# ET2.net
KiCad netlist of a schematic drawn in EAGLE
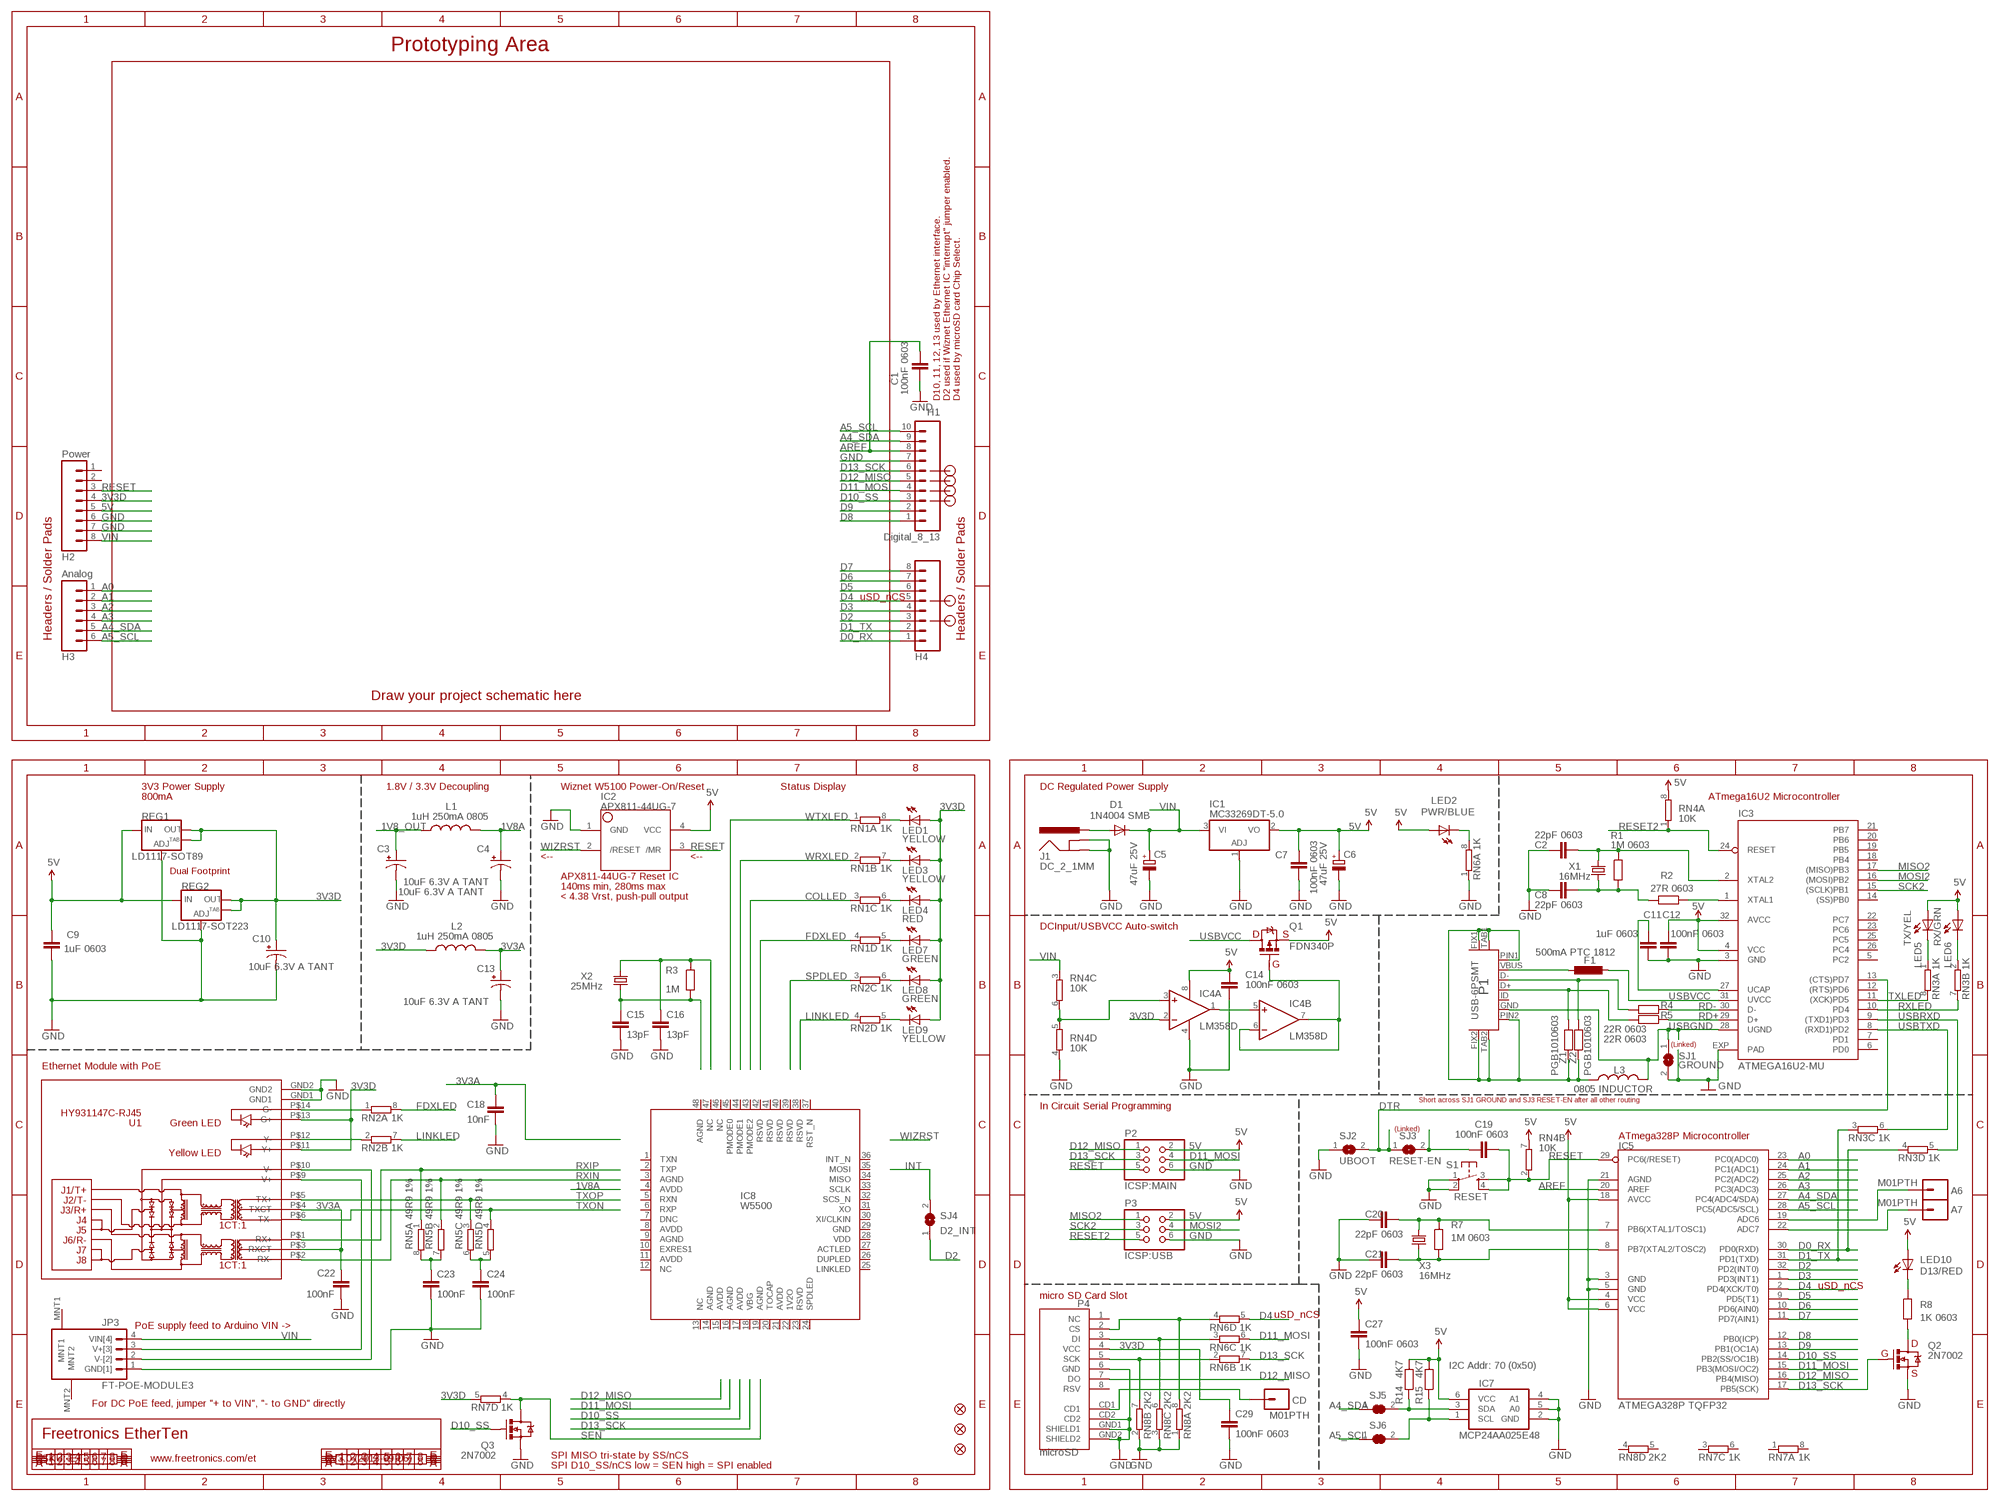
[diagram p0: schematic, sheet 1]

(export (version "E")
  (design (tool "Eeschema 10.0.6"))
  (components
    (comp (ref "A6")
      (value "M01PTH")
      (footprint "eagle-import:1X01")
      (libsource (lib "eagle-import") (part "M01PTH"))
    )
    (comp (ref "A7")
      (value "M01PTH")
      (footprint "eagle-import:1X01")
      (libsource (lib "eagle-import") (part "M01PTH"))
    )
    (comp (ref "C1")
      (value "100nF 0603")
      (footprint "eagle-import:0603")
      (libsource (lib "eagle-import") (part "CAP0603"))
    )
    (comp (ref "C2")
      (value "22pF 0603")
      (footprint "eagle-import:0603")
      (libsource (lib "eagle-import") (part "CAP0603"))
    )
    (comp (ref "C3")
      (value "10uF 6.3V A TANT")
      (footprint "eagle-import:EIA3216")
      (libsource (lib "eagle-import") (part "CAP_POL1206"))
    )
    (comp (ref "C4")
      (value "10uF 6.3V A TANT")
      (footprint "eagle-import:EIA3216")
      (libsource (lib "eagle-import") (part "CAP_POL1206"))
    )
    (comp (ref "C5")
      (value "47uF 25V")
      (footprint "eagle-import:PANASONIC_D")
      (libsource (lib "eagle-import") (part "CPOL-EUD"))
    )
    (comp (ref "C6")
      (value "47uF 25V")
      (footprint "eagle-import:PANASONIC_D")
      (libsource (lib "eagle-import") (part "CPOL-EUD"))
    )
    (comp (ref "C7")
      (value "100nF 0603")
      (footprint "eagle-import:0603")
      (libsource (lib "eagle-import") (part "CAP0603"))
    )
    (comp (ref "C8")
      (value "22pF 0603")
      (footprint "eagle-import:0603")
      (libsource (lib "eagle-import") (part "CAP0603"))
    )
    (comp (ref "C9")
      (value "1uF 0603")
      (footprint "eagle-import:0603")
      (libsource (lib "eagle-import") (part "CAP0603"))
    )
    (comp (ref "C10")
      (value "10uF 6.3V A TANT")
      (footprint "eagle-import:EIA3216")
      (libsource (lib "eagle-import") (part "CAP_POL1206"))
    )
    (comp (ref "C11")
      (value "1uF 0603")
      (footprint "eagle-import:0603")
      (libsource (lib "eagle-import") (part "CAP0603"))
    )
    (comp (ref "C12")
      (value "100nF 0603")
      (footprint "eagle-import:0603")
      (libsource (lib "eagle-import") (part "CAP0603"))
    )
    (comp (ref "C13")
      (value "10uF 6.3V A TANT")
      (footprint "eagle-import:EIA3216")
      (libsource (lib "eagle-import") (part "CAP_POL1206"))
    )
    (comp (ref "C14")
      (value "100nF 0603")
      (footprint "eagle-import:0603")
      (libsource (lib "eagle-import") (part "CAP0603"))
    )
    (comp (ref "C15")
      (value "13pF")
      (footprint "eagle-import:0603")
      (libsource (lib "eagle-import") (part "CAP0603"))
    )
    (comp (ref "C16")
      (value "13pF")
      (footprint "eagle-import:0603")
      (libsource (lib "eagle-import") (part "CAP0603"))
    )
    (comp (ref "C18")
      (value "10nF")
      (footprint "eagle-import:0603")
      (libsource (lib "eagle-import") (part "CAP0603"))
    )
    (comp (ref "C19")
      (value "100nF 0603")
      (footprint "eagle-import:0603")
      (libsource (lib "eagle-import") (part "CAP0603"))
    )
    (comp (ref "C20")
      (value "22pF 0603")
      (footprint "eagle-import:0603")
      (libsource (lib "eagle-import") (part "CAP0603"))
    )
    (comp (ref "C21")
      (value "22pF 0603")
      (footprint "eagle-import:0603")
      (libsource (lib "eagle-import") (part "CAP0603"))
    )
    (comp (ref "C22")
      (value "100nF")
      (footprint "eagle-import:0603")
      (libsource (lib "eagle-import") (part "CAP0603"))
    )
    (comp (ref "C23")
      (value "100nF")
      (footprint "eagle-import:0603")
      (libsource (lib "eagle-import") (part "CAP0603"))
    )
    (comp (ref "C24")
      (value "100nF")
      (footprint "eagle-import:0603")
      (libsource (lib "eagle-import") (part "CAP0603"))
    )
    (comp (ref "C27")
      (value "100nF 0603")
      (footprint "eagle-import:0603")
      (libsource (lib "eagle-import") (part "CAP0603"))
    )
    (comp (ref "C29")
      (value "100nF 0603")
      (footprint "eagle-import:0603")
      (libsource (lib "eagle-import") (part "CAP0603"))
    )
    (comp (ref "CD")
      (value "M01PTH")
      (footprint "eagle-import:1X01")
      (libsource (lib "eagle-import") (part "M01PTH"))
    )
    (comp (ref "D1")
      (value "1N4004 SMB")
      (footprint "eagle-import:SMB-DIODE")
      (libsource (lib "eagle-import") (part "DIODESMB"))
    )
    (comp (ref "F1")
      (value "500mA PTC 1812")
      (footprint "eagle-import:L1812")
      (libsource (lib "eagle-import") (part "L-EUL1812"))
    )
    (comp (ref "FID1")
      (value "FIDUCIAL1X2.5")
      (footprint "eagle-import:FIDUCIAL-1X2.5")
      (libsource (lib "eagle-import") (part "FIDUCIAL1X2.5"))
    )
    (comp (ref "FID2")
      (value "FIDUCIAL1X2.5")
      (footprint "eagle-import:FIDUCIAL-1X2.5")
      (libsource (lib "eagle-import") (part "FIDUCIAL1X2.5"))
    )
    (comp (ref "FID3")
      (value "FIDUCIAL1X2.5")
      (footprint "eagle-import:FIDUCIAL-1X2.5")
      (libsource (lib "eagle-import") (part "FIDUCIAL1X2.5"))
    )
    (comp (ref "H1")
      (value "Digital_8_13")
      (footprint "eagle-import:1X10")
      (libsource (lib "eagle-import") (part "M100.1"))
    )
    (comp (ref "H2")
      (value "Power")
      (footprint "eagle-import:1X08")
      (libsource (lib "eagle-import") (part "freetronics-master-v1_M08"))
    )
    (comp (ref "H3")
      (value "Analog")
      (footprint "eagle-import:1X06")
      (libsource (lib "eagle-import") (part "M06SIP"))
    )
    (comp (ref "H4")
      (value "Digital_0_7")
      (footprint "eagle-import:1X08")
      (libsource (lib "eagle-import") (part "M08"))
    )
    (comp (ref "IC1")
      (value "MC33269DT-5.0")
      (footprint "eagle-import:DPACK")
      (libsource (lib "eagle-import") (part "MC33269?D-5.0"))
    )
    (comp (ref "IC2")
      (value "APX811-44UG-7")
      (footprint "eagle-import:SOT143-R")
      (libsource (lib "eagle-import") (part "APX81X-RESET-IC"))
    )
    (comp (ref "IC3")
      (value "ATMEGA16U2-MU")
      (footprint "eagle-import:ATMEL_QFN32")
      (libsource (lib "eagle-import") (part "ATMEL_ATMEGA8U2-MUQFN"))
    )
    (comp (ref "IC4")
      (value "LM358D")
      (footprint "eagle-import:SO08")
      (libsource (lib "eagle-import") (part "LM358D"))
    )
    (comp (ref "IC5")
      (value "ATMEGA328P TQFP32")
      (footprint "eagle-import:TQFP32-08")
      (libsource (lib "eagle-import") (part "AVR-MEGA8-AI"))
    )
    (comp (ref "IC7")
      (value "MCP24AA025E48")
      (footprint "eagle-import:SOT23-6")
      (libsource (lib "eagle-import") (part "MCP24AA025E48"))
    )
    (comp (ref "IC8")
      (value "W5500")
      (footprint "eagle-import:W5500")
      (libsource (lib "eagle-import") (part "W5500"))
    )
    (comp (ref "J1")
      (value "DC_2_1MM")
      (footprint "eagle-import:POWER_JACK_PTH")
      (libsource (lib "eagle-import") (part "POWER_JACKPTH"))
    )
    (comp (ref "JP3")
      (value "FT-POE-MODULE3")
      (footprint "eagle-import:FT-POE-MODULE-NOLABEL")
      (libsource (lib "eagle-import") (part "FT-POE-MODULE3"))
    )
    (comp (ref "L1")
      (value "1uH 250mA 0805")
      (footprint "eagle-import:L2012C")
      (libsource (lib "eagle-import") (part "L-USL2012C"))
    )
    (comp (ref "L2")
      (value "1uH 250mA 0805")
      (footprint "eagle-import:L2012C")
      (libsource (lib "eagle-import") (part "L-USL2012C"))
    )
    (comp (ref "L3")
      (value "0805 INDUCTOR")
      (footprint "eagle-import:0805-LARGE")
      (libsource (lib "eagle-import") (part "INDUCTOR0805-LARGE"))
    )
    (comp (ref "LED1")
      (value "YELLOW")
      (footprint "eagle-import:LED-0603")
      (libsource (lib "eagle-import") (part "LED0603"))
    )
    (comp (ref "LED2")
      (value "PWR/BLUE")
      (footprint "eagle-import:LED-0603")
      (libsource (lib "eagle-import") (part "LED0603"))
    )
    (comp (ref "LED3")
      (value "YELLOW")
      (footprint "eagle-import:LED-0603")
      (libsource (lib "eagle-import") (part "LED0603"))
    )
    (comp (ref "LED4")
      (value "RED")
      (footprint "eagle-import:LED-0603")
      (libsource (lib "eagle-import") (part "LED0603"))
    )
    (comp (ref "LED5")
      (value "TX/YEL")
      (footprint "eagle-import:LED-0603")
      (libsource (lib "eagle-import") (part "LED0603"))
    )
    (comp (ref "LED6")
      (value "RX/GRN")
      (footprint "eagle-import:LED-0603")
      (libsource (lib "eagle-import") (part "LED0603"))
    )
    (comp (ref "LED7")
      (value "GREEN")
      (footprint "eagle-import:LED-0603")
      (libsource (lib "eagle-import") (part "LED0603"))
    )
    (comp (ref "LED8")
      (value "GREEN")
      (footprint "eagle-import:LED-0603")
      (libsource (lib "eagle-import") (part "LED0603"))
    )
    (comp (ref "LED9")
      (value "YELLOW")
      (footprint "eagle-import:LED-0603")
      (libsource (lib "eagle-import") (part "LED0603"))
    )
    (comp (ref "LED10")
      (value "D13/RED")
      (footprint "eagle-import:LED-0603")
      (libsource (lib "eagle-import") (part "LED0603"))
    )
    (comp (ref "P1")
      (value "USB-6PSMT")
      (footprint "eagle-import:USB-MICROB-MB05PMXX")
      (libsource (lib "eagle-import") (part "USB-6PSMT"))
    )
    (comp (ref "P2")
      (value "ICSP:MAIN")
      (footprint "eagle-import:2X03")
      (libsource (lib "eagle-import") (part "PINHD-2X3"))
    )
    (comp (ref "P3")
      (value "ICSP:USB")
      (footprint "eagle-import:2X03")
      (libsource (lib "eagle-import") (part "PINHD-2X3"))
    )
    (comp (ref "P4")
      (value "microSD")
      (footprint "eagle-import:MICRO-SD-SOCKET-PP")
      (libsource (lib "eagle-import") (part "USD-SOCKETNEW"))
    )
    (comp (ref "Q1")
      (value "FDN340P")
      (footprint "eagle-import:SOT23")
      (libsource (lib "eagle-import") (part "MOSFET-PCHANNEL"))
    )
    (comp (ref "Q2")
      (value "2N7002")
      (footprint "eagle-import:SOT23-3")
      (libsource (lib "eagle-import") (part "MOSFET-NCHANNELSMD"))
    )
    (comp (ref "Q3")
      (value "2N7002")
      (footprint "eagle-import:SOT23-3")
      (libsource (lib "eagle-import") (part "MOSFET-NCHANNELSMD"))
    )
    (comp (ref "R1")
      (value "1M 0603")
      (footprint "eagle-import:0603")
      (libsource (lib "eagle-import") (part "RESISTOR0603"))
    )
    (comp (ref "R2")
      (value "27R 0603")
      (footprint "eagle-import:0603")
      (libsource (lib "eagle-import") (part "RESISTOR0603"))
    )
    (comp (ref "R3")
      (value "1M")
      (footprint "eagle-import:0603")
      (libsource (lib "eagle-import") (part "RESISTOR0603"))
    )
    (comp (ref "R4")
      (value "22R 0603")
      (footprint "eagle-import:0603")
      (libsource (lib "eagle-import") (part "RESISTOR0603"))
    )
    (comp (ref "R5")
      (value "22R 0603")
      (footprint "eagle-import:0603")
      (libsource (lib "eagle-import") (part "RESISTOR0603"))
    )
    (comp (ref "R7")
      (value "1M 0603")
      (footprint "eagle-import:0603")
      (libsource (lib "eagle-import") (part "RESISTOR0603"))
    )
    (comp (ref "R8")
      (value "1K 0603")
      (footprint "eagle-import:0603")
      (libsource (lib "eagle-import") (part "RESISTOR0603"))
    )
    (comp (ref "R14")
      (value "4K7")
      (footprint "eagle-import:0603")
      (libsource (lib "eagle-import") (part "freetronics-master-v1.1_RESISTOR0603"))
    )
    (comp (ref "R15")
      (value "4K7")
      (footprint "eagle-import:0603")
      (libsource (lib "eagle-import") (part "freetronics-master-v1.1_RESISTOR0603"))
    )
    (comp (ref "REG1")
      (value "LD1117-SOT89")
      (footprint "eagle-import:SOT89")
      (libsource (lib "eagle-import") (part "V_REG_LM1117SOT89"))
    )
    (comp (ref "REG2")
      (value "LD1117-SOT223")
      (footprint "eagle-import:SOT223")
      (libsource (lib "eagle-import") (part "V_REG_LM1117SOT223"))
    )
    (comp (ref "RN1")
      (value "1K")
      (footprint "eagle-import:CAY16")
      (libsource (lib "eagle-import") (part "4R-NCAY16"))
    )
    (comp (ref "RN2")
      (value "1K")
      (footprint "eagle-import:CAY16")
      (libsource (lib "eagle-import") (part "4R-NCAY16"))
    )
    (comp (ref "RN3")
      (value "1K")
      (footprint "eagle-import:CAY16")
      (libsource (lib "eagle-import") (part "4R-NCAY16"))
    )
    (comp (ref "RN4")
      (value "10K")
      (footprint "eagle-import:CAY16")
      (libsource (lib "eagle-import") (part "4R-NCAY16"))
    )
    (comp (ref "RN5")
      (value "49R9 1%")
      (footprint "eagle-import:CAY16")
      (libsource (lib "eagle-import") (part "4R-NCAY16"))
    )
    (comp (ref "RN6")
      (value "1K")
      (footprint "eagle-import:CAY16")
      (libsource (lib "eagle-import") (part "4R-NCAY16"))
    )
    (comp (ref "RN7")
      (value "1K")
      (footprint "eagle-import:CAY16")
      (libsource (lib "eagle-import") (part "4R-NCAY16"))
    )
    (comp (ref "RN8")
      (value "2K2")
      (footprint "eagle-import:CAY16")
      (libsource (lib "eagle-import") (part "4R-NCAY16"))
    )
    (comp (ref "S1")
      (value "RESET")
      (footprint "eagle-import:TACTILE_SWITCH_SMD")
      (libsource (lib "eagle-import") (part "TAC_SWITCHSMD"))
    )
    (comp (ref "SJ1")
      (value "GROUND")
      (footprint "eagle-import:SJ")
      (libsource (lib "eagle-import") (part "SJ"))
    )
    (comp (ref "SJ2")
      (value "UBOOT")
      (footprint "eagle-import:SJ")
      (libsource (lib "eagle-import") (part "SJ"))
    )
    (comp (ref "SJ3")
      (value "RESET-EN")
      (footprint "eagle-import:SJ")
      (libsource (lib "eagle-import") (part "SJ"))
    )
    (comp (ref "SJ4")
      (value "D2_INT")
      (footprint "eagle-import:SJ")
      (libsource (lib "eagle-import") (part "SJ"))
    )
    (comp (ref "SJ5")
      (value "SJCN")
      (footprint "eagle-import:SJC")
      (libsource (lib "eagle-import") (part "SJCN"))
    )
    (comp (ref "SJ6")
      (value "SJCN")
      (footprint "eagle-import:SJC")
      (libsource (lib "eagle-import") (part "SJCN"))
    )
    (comp (ref "U1")
      (value "HY931147C-RJ45")
      (footprint "eagle-import:HY931147C")
      (libsource (lib "eagle-import") (part "HY931147C-RJ45"))
    )
    (comp (ref "X1")
      (value "16MHz")
      (footprint "eagle-import:HC49U-V")
      (libsource (lib "eagle-import") (part "CRYSTALHC49UV"))
    )
    (comp (ref "X2")
      (value "25MHz")
      (footprint "eagle-import:HC49U-V")
      (libsource (lib "eagle-import") (part "CRYSTALHC49UV"))
    )
    (comp (ref "X3")
      (value "16MHz")
      (footprint "eagle-import:HC49U-V")
      (libsource (lib "eagle-import") (part "CRYSTALHC49UV"))
    )
    (comp (ref "Z1")
      (value "PGB1010603")
      (footprint "eagle-import:0603")
      (libsource (lib "eagle-import") (part "RESISTOR0603"))
    )
    (comp (ref "Z2")
      (value "PGB1010603")
      (footprint "eagle-import:0603")
      (libsource (lib "eagle-import") (part "RESISTOR0603"))
    )
  )
  (nets
    (net (code "1") (name "/1V8A") (class "Default")
      (node (ref "C4") (pin "A") (pinfunction "+_A") (pintype "passive"))
      (node (ref "L1") (pin "2") (pinfunction "2_2") (pintype "passive"))
    )
    (net (code "2") (name "/1V8_OUT") (class "Default")
      (node (ref "C3") (pin "A") (pinfunction "+_A") (pintype "passive"))
      (node (ref "L1") (pin "1") (pinfunction "1_1") (pintype "passive"))
    )
    (net (code "3") (name "/3V3A") (class "Default")
      (node (ref "C13") (pin "A") (pinfunction "+_A") (pintype "passive"))
      (node (ref "C18") (pin "1") (pinfunction "1_1") (pintype "passive"))
      (node (ref "C22") (pin "1") (pinfunction "1_1") (pintype "passive"))
      (node (ref "L2") (pin "2") (pinfunction "2_2") (pintype "passive"))
      (node (ref "U1") (pin "P$3") (pinfunction "RXCT_P$3") (pintype "bidirectional"))
      (node (ref "U1") (pin "P$4") (pinfunction "TXCT_P$4") (pintype "bidirectional"))
    )
    (net (code "4") (name "/3V3D") (class "Default")
      (node (ref "C10") (pin "A") (pinfunction "+_A") (pintype "passive"))
      (node (ref "C29") (pin "1") (pinfunction "1_1") (pintype "passive"))
      (node (ref "H2") (pin "4") (pinfunction "4_4") (pintype "passive"))
      (node (ref "IC4") (pin "2") (pinfunction "-IN_2") (pintype "input"))
      (node (ref "L2") (pin "1") (pinfunction "1_1") (pintype "passive"))
      (node (ref "LED1") (pin "A") (pinfunction "A_A") (pintype "passive"))
      (node (ref "LED3") (pin "A") (pinfunction "A_A") (pintype "passive"))
      (node (ref "LED4") (pin "A") (pinfunction "A_A") (pintype "passive"))
      (node (ref "LED7") (pin "A") (pinfunction "A_A") (pintype "passive"))
      (node (ref "LED8") (pin "A") (pinfunction "A_A") (pintype "passive"))
      (node (ref "LED9") (pin "A") (pinfunction "A_A") (pintype "passive"))
      (node (ref "P4") (pin "4") (pinfunction "VCC_4") (pintype "bidirectional"))
      (node (ref "REG1") (pin "2") (pinfunction "OUT_2") (pintype "output"))
      (node (ref "REG1") (pin "4") (pinfunction "OUT_4") (pintype "output"))
      (node (ref "REG2") (pin "2") (pinfunction "OUT_2") (pintype "output"))
      (node (ref "REG2") (pin "4") (pinfunction "OUT_4") (pintype "output"))
      (node (ref "RN7") (pin "5") (pinfunction "2_5") (pintype "passive"))
      (node (ref "U1") (pin "P$11") (pinfunction "Y+_P$11") (pintype "bidirectional"))
      (node (ref "U1") (pin "P$13") (pinfunction "G+_P$13") (pintype "bidirectional"))
    )
    (net (code "5") (name "/A0") (class "Default")
      (node (ref "H3") (pin "1") (pinfunction "1_1") (pintype "passive"))
      (node (ref "IC5") (pin "23") (pinfunction "PC0(ADC0)_23") (pintype "bidirectional"))
    )
    (net (code "6") (name "/A1") (class "Default")
      (node (ref "H3") (pin "2") (pinfunction "2_2") (pintype "passive"))
      (node (ref "IC5") (pin "24") (pinfunction "PC1(ADC1)_24") (pintype "bidirectional"))
    )
    (net (code "7") (name "/A2") (class "Default")
      (node (ref "H3") (pin "3") (pinfunction "3_3") (pintype "passive"))
      (node (ref "IC5") (pin "25") (pinfunction "PC2(ADC2)_25") (pintype "bidirectional"))
    )
    (net (code "8") (name "/A3") (class "Default")
      (node (ref "H3") (pin "4") (pinfunction "4_4") (pintype "passive"))
      (node (ref "IC5") (pin "26") (pinfunction "PC3(ADC3)_26") (pintype "bidirectional"))
    )
    (net (code "9") (name "/A4_SDA") (class "Default")
      (node (ref "H1") (pin "9") (pinfunction "9_9") (pintype "passive"))
      (node (ref "H3") (pin "5") (pinfunction "5_5") (pintype "passive"))
      (node (ref "IC5") (pin "27") (pinfunction "PC4(ADC4/SDA)_27") (pintype "bidirectional"))
      (node (ref "SJ5") (pin "1") (pinfunction "1_1") (pintype "passive"))
    )
    (net (code "10") (name "/A5_SCL") (class "Default")
      (node (ref "H1") (pin "10") (pinfunction "10_10") (pintype "passive"))
      (node (ref "H3") (pin "6") (pinfunction "6_6") (pintype "passive"))
      (node (ref "IC5") (pin "28") (pinfunction "PC5(ADC5/SCL)_28") (pintype "bidirectional"))
      (node (ref "SJ6") (pin "1") (pinfunction "1_1") (pintype "passive"))
    )
    (net (code "11") (name "/AREF") (class "Default")
      (node (ref "C1") (pin "1") (pinfunction "1_1") (pintype "passive"))
      (node (ref "H1") (pin "8") (pinfunction "8_8") (pintype "passive"))
      (node (ref "IC5") (pin "20") (pinfunction "AREF_20") (pintype "bidirectional"))
    )
    (net (code "12") (name "/COLLED") (class "Default")
      (node (ref "RN1") (pin "3") (pinfunction "1_3") (pintype "passive"))
    )
    (net (code "13") (name "/D0_RX") (class "Default")
      (node (ref "H4") (pin "1") (pinfunction "1_1") (pintype "passive"))
      (node (ref "IC5") (pin "30") (pinfunction "PD0(RXD)_30") (pintype "bidirectional"))
      (node (ref "RN3") (pin "4") (pinfunction "1_4") (pintype "passive"))
    )
    (net (code "14") (name "/D1_TX") (class "Default")
      (node (ref "H4") (pin "2") (pinfunction "2_2") (pintype "passive"))
      (node (ref "IC5") (pin "31") (pinfunction "PD1(TXD)_31") (pintype "bidirectional"))
      (node (ref "RN3") (pin "3") (pinfunction "1_3") (pintype "passive"))
    )
    (net (code "15") (name "/D2") (class "Default")
      (node (ref "H4") (pin "3") (pinfunction "3_3") (pintype "passive"))
      (node (ref "IC5") (pin "32") (pinfunction "PD2(INT0)_32") (pintype "bidirectional"))
      (node (ref "SJ4") (pin "1") (pinfunction "1_1") (pintype "passive"))
    )
    (net (code "16") (name "/D3") (class "Default")
      (node (ref "H4") (pin "4") (pinfunction "4_4") (pintype "passive"))
      (node (ref "IC5") (pin "1") (pinfunction "PD3(INT1)_1") (pintype "bidirectional"))
    )
    (net (code "17") (name "/D4") (class "Default")
      (node (ref "H4") (pin "5") (pinfunction "5_5") (pintype "passive"))
      (node (ref "IC5") (pin "2") (pinfunction "PD4(XCK/T0)_2") (pintype "bidirectional"))
      (node (ref "RN6") (pin "5") (pinfunction "2_5") (pintype "passive"))
    )
    (net (code "18") (name "/D5") (class "Default")
      (node (ref "H4") (pin "6") (pinfunction "6_6") (pintype "passive"))
      (node (ref "IC5") (pin "9") (pinfunction "PD5(T1)_9") (pintype "bidirectional"))
    )
    (net (code "19") (name "/D6") (class "Default")
      (node (ref "H4") (pin "7") (pinfunction "7_7") (pintype "passive"))
      (node (ref "IC5") (pin "10") (pinfunction "PD6(AIN0)_10") (pintype "bidirectional"))
    )
    (net (code "20") (name "/D7") (class "Default")
      (node (ref "H4") (pin "8") (pinfunction "8_8") (pintype "passive"))
      (node (ref "IC5") (pin "11") (pinfunction "PD7(AIN1)_11") (pintype "bidirectional"))
    )
    (net (code "21") (name "/D8") (class "Default")
      (node (ref "H1") (pin "1") (pinfunction "1_1") (pintype "passive"))
      (node (ref "IC5") (pin "12") (pinfunction "PB0(ICP)_12") (pintype "bidirectional"))
    )
    (net (code "22") (name "/D9") (class "Default")
      (node (ref "H1") (pin "2") (pinfunction "2_2") (pintype "passive"))
      (node (ref "IC5") (pin "13") (pinfunction "PB1(OC1A)_13") (pintype "bidirectional"))
    )
    (net (code "23") (name "/D10_SS") (class "Default")
      (node (ref "H1") (pin "3") (pinfunction "3_3") (pintype "passive"))
      (node (ref "IC5") (pin "14") (pinfunction "PB2(SS/OC1B)_14") (pintype "bidirectional"))
      (node (ref "Q3") (pin "1") (pinfunction "G_1") (pintype "passive"))
    )
    (net (code "24") (name "/D11_MOSI") (class "Default")
      (node (ref "H1") (pin "4") (pinfunction "4_4") (pintype "passive"))
      (node (ref "IC5") (pin "15") (pinfunction "PB3(MOSI/OC2)_15") (pintype "bidirectional"))
      (node (ref "P2") (pin "4") (pinfunction "4_4") (pintype "passive"))
      (node (ref "RN6") (pin "6") (pinfunction "2_6") (pintype "passive"))
    )
    (net (code "25") (name "/D12_MISO") (class "Default")
      (node (ref "H1") (pin "5") (pinfunction "5_5") (pintype "passive"))
      (node (ref "IC5") (pin "16") (pinfunction "PB4(MISO)_16") (pintype "bidirectional"))
      (node (ref "P2") (pin "1") (pinfunction "1_1") (pintype "passive"))
      (node (ref "P4") (pin "7") (pinfunction "DO_7") (pintype "bidirectional"))
    )
    (net (code "26") (name "/D13_SCK") (class "Default")
      (node (ref "H1") (pin "6") (pinfunction "6_6") (pintype "passive"))
      (node (ref "IC5") (pin "17") (pinfunction "PB5(SCK)_17") (pintype "bidirectional"))
      (node (ref "P2") (pin "3") (pinfunction "3_3") (pintype "passive"))
      (node (ref "Q2") (pin "1") (pinfunction "G_1") (pintype "passive"))
      (node (ref "RN6") (pin "7") (pinfunction "2_7") (pintype "passive"))
    )
    (net (code "27") (name "/DTR") (class "Default")
      (node (ref "IC3") (pin "13") (pinfunction "(CTS)PD7_13") (pintype "bidirectional"))
      (node (ref "SJ2") (pin "2") (pinfunction "2_2") (pintype "passive"))
      (node (ref "SJ3") (pin "1") (pinfunction "1_1") (pintype "passive"))
    )
    (net (code "28") (name "/FDXLED") (class "Default")
      (node (ref "RN1") (pin "4") (pinfunction "1_4") (pintype "passive"))
      (node (ref "RN2") (pin "8") (pinfunction "2_8") (pintype "passive"))
    )
    (net (code "29") (name "/INT") (class "Default")
      (node (ref "SJ4") (pin "2") (pinfunction "2_2") (pintype "passive"))
    )
    (net (code "30") (name "/LINKLED") (class "Default")
      (node (ref "RN2") (pin "4") (pinfunction "1_4") (pintype "passive"))
      (node (ref "RN2") (pin "7") (pinfunction "2_7") (pintype "passive"))
    )
    (net (code "31") (name "/MISO2") (class "Default")
      (node (ref "IC3") (pin "17") (pinfunction "(MISO)PB3_17") (pintype "bidirectional"))
      (node (ref "P3") (pin "1") (pinfunction "1_1") (pintype "passive"))
    )
    (net (code "32") (name "/MOSI2") (class "Default")
      (node (ref "IC3") (pin "16") (pinfunction "(MOSI)PB2_16") (pintype "bidirectional"))
      (node (ref "P3") (pin "4") (pinfunction "4_4") (pintype "passive"))
    )
    (net (code "33") (name "/RD+") (class "Default")
      (node (ref "IC3") (pin "29") (pinfunction "D+_29") (pintype "bidirectional"))
      (node (ref "R5") (pin "1") (pinfunction "1_1") (pintype "passive"))
    )
    (net (code "34") (name "/RD-") (class "Default")
      (node (ref "IC3") (pin "30") (pinfunction "D-_30") (pintype "bidirectional"))
      (node (ref "R4") (pin "1") (pinfunction "1_1") (pintype "passive"))
    )
    (net (code "35") (name "/RESET") (class "Default")
      (node (ref "C19") (pin "2") (pinfunction "2_2") (pintype "passive"))
      (node (ref "H2") (pin "3") (pinfunction "3_3") (pintype "passive"))
      (node (ref "IC2") (pin "3") (pinfunction "/MR_3") (pintype "input"))
      (node (ref "IC5") (pin "29") (pinfunction "PC6(/RESET)_29") (pintype "bidirectional"))
      (node (ref "P2") (pin "5") (pinfunction "5_5") (pintype "passive"))
      (node (ref "RN4") (pin "2") (pinfunction "1_2") (pintype "passive"))
      (node (ref "S1") (pin "3") (pinfunction "3_3") (pintype "passive"))
      (node (ref "S1") (pin "4") (pinfunction "4_4") (pintype "passive"))
    )
    (net (code "36") (name "/RESET2") (class "Default")
      (node (ref "IC3") (pin "24") (pinfunction "RESET_24") (pintype "input"))
      (node (ref "P3") (pin "5") (pinfunction "5_5") (pintype "passive"))
      (node (ref "RN4") (pin "1") (pinfunction "1_1") (pintype "passive"))
    )
    (net (code "37") (name "/RXIN") (class "Default")
      (node (ref "RN5") (pin "2") (pinfunction "1_2") (pintype "passive"))
      (node (ref "U1") (pin "P$2") (pinfunction "RX-_P$2") (pintype "bidirectional"))
    )
    (net (code "38") (name "/RXIP") (class "Default")
      (node (ref "RN5") (pin "1") (pinfunction "1_1") (pintype "passive"))
      (node (ref "U1") (pin "P$1") (pinfunction "RX+_P$1") (pintype "bidirectional"))
    )
    (net (code "39") (name "/RXLED") (class "Default")
      (node (ref "IC3") (pin "10") (pinfunction "PD4_10") (pintype "bidirectional"))
      (node (ref "RN3") (pin "7") (pinfunction "2_7") (pintype "passive"))
    )
    (net (code "40") (name "/SCK2") (class "Default")
      (node (ref "IC3") (pin "15") (pinfunction "(SCLK)PB1_15") (pintype "bidirectional"))
      (node (ref "P3") (pin "3") (pinfunction "3_3") (pintype "passive"))
    )
    (net (code "41") (name "/SEN") (class "Default")
      (node (ref "Q3") (pin "3") (pinfunction "D_3") (pintype "passive"))
      (node (ref "RN7") (pin "4") (pinfunction "1_4") (pintype "passive"))
    )
    (net (code "42") (name "/SPDLED") (class "Default")
      (node (ref "RN2") (pin "3") (pinfunction "1_3") (pintype "passive"))
    )
    (net (code "43") (name "/TXLED") (class "Default")
      (node (ref "IC3") (pin "11") (pinfunction "(XCK)PD5_11") (pintype "bidirectional"))
      (node (ref "RN3") (pin "8") (pinfunction "2_8") (pintype "passive"))
    )
    (net (code "44") (name "/TXON") (class "Default")
      (node (ref "RN5") (pin "4") (pinfunction "1_4") (pintype "passive"))
      (node (ref "U1") (pin "P$6") (pinfunction "TX-_P$6") (pintype "bidirectional"))
    )
    (net (code "45") (name "/TXOP") (class "Default")
      (node (ref "RN5") (pin "3") (pinfunction "1_3") (pintype "passive"))
      (node (ref "U1") (pin "P$5") (pinfunction "TX+_P$5") (pintype "bidirectional"))
    )
    (net (code "46") (name "/USBGND") (class "Default")
      (node (ref "IC3") (pin "28") (pinfunction "UGND_28") (pintype "power_in"))
      (node (ref "L3") (pin "2") (pinfunction "2_2") (pintype "passive"))
      (node (ref "P1") (pin "GND") (pinfunction "GND_GND") (pintype "bidirectional"))
      (node (ref "SJ1") (pin "1") (pinfunction "1_1") (pintype "passive"))
    )
    (net (code "47") (name "/USBRXD") (class "Default")
      (node (ref "IC3") (pin "9") (pinfunction "(TXD1)PD3_9") (pintype "bidirectional"))
      (node (ref "RN3") (pin "5") (pinfunction "2_5") (pintype "passive"))
    )
    (net (code "48") (name "/USBTXD") (class "Default")
      (node (ref "IC3") (pin "8") (pinfunction "(RXD1)PD2_8") (pintype "bidirectional"))
      (node (ref "RN3") (pin "6") (pinfunction "2_6") (pintype "passive"))
    )
    (net (code "49") (name "/USBVCC") (class "Default")
      (node (ref "F1") (pin "2") (pinfunction "2_2") (pintype "passive"))
      (node (ref "IC3") (pin "31") (pinfunction "UVCC_31") (pintype "power_in"))
      (node (ref "Q1") (pin "3") (pinfunction "D_3") (pintype "passive"))
    )
    (net (code "50") (name "/VIN") (class "Default")
      (node (ref "C5") (pin "+") (pinfunction "+_+") (pintype "passive"))
      (node (ref "D1") (pin "C") (pinfunction "C_C") (pintype "passive"))
      (node (ref "H2") (pin "8") (pinfunction "8_8") (pintype "passive"))
      (node (ref "IC1") (pin "3") (pinfunction "VI_3") (pintype "input"))
      (node (ref "JP3") (pin "4") (pinfunction "VIN[4]_4") (pintype "passive"))
      (node (ref "RN4") (pin "3") (pinfunction "1_3") (pintype "passive"))
    )
    (net (code "51") (name "/WIZRST") (class "Default")
      (node (ref "IC2") (pin "2") (pinfunction "/RESET_2") (pintype "output"))
    )
    (net (code "52") (name "/WRXLED") (class "Default")
      (node (ref "RN1") (pin "2") (pinfunction "1_2") (pintype "passive"))
    )
    (net (code "53") (name "/WTXLED") (class "Default")
      (node (ref "RN1") (pin "1") (pinfunction "1_1") (pintype "passive"))
    )
    (net (code "54") (name "5V") (class "Default")
      (node (ref "C12") (pin "1") (pinfunction "1_1") (pintype "passive"))
      (node (ref "C14") (pin "1") (pinfunction "1_1") (pintype "passive"))
      (node (ref "C27") (pin "1") (pinfunction "1_1") (pintype "passive"))
      (node (ref "C6") (pin "+") (pinfunction "+_+") (pintype "passive"))
      (node (ref "C7") (pin "1") (pinfunction "1_1") (pintype "passive"))
      (node (ref "C9") (pin "1") (pinfunction "1_1") (pintype "passive"))
      (node (ref "H2") (pin "5") (pinfunction "5_5") (pintype "passive"))
      (node (ref "IC1") (pin "2") (pinfunction "VO_2") (pintype "passive"))
      (node (ref "IC2") (pin "4") (pinfunction "VCC_4") (pintype "power_in"))
      (node (ref "IC3") (pin "32") (pinfunction "AVCC_32") (pintype "power_in"))
      (node (ref "IC3") (pin "4") (pinfunction "VCC_4") (pintype "power_in"))
      (node (ref "IC4") (pin "8") (pinfunction "V+_8") (pintype "power_in"))
      (node (ref "IC5") (pin "18") (pinfunction "AVCC_18") (pintype "bidirectional"))
      (node (ref "IC5") (pin "4") (pinfunction "VCC_4") (pintype "bidirectional"))
      (node (ref "IC5") (pin "6") (pinfunction "VCC_6") (pintype "bidirectional"))
      (node (ref "IC7") (pin "6") (pinfunction "VCC_6") (pintype "power_in"))
      (node (ref "LED10") (pin "A") (pinfunction "A_A") (pintype "passive"))
      (node (ref "LED2") (pin "A") (pinfunction "A_A") (pintype "passive"))
      (node (ref "LED5") (pin "A") (pinfunction "A_A") (pintype "passive"))
      (node (ref "LED6") (pin "A") (pinfunction "A_A") (pintype "passive"))
      (node (ref "P2") (pin "2") (pinfunction "2_2") (pintype "passive"))
      (node (ref "P3") (pin "2") (pinfunction "2_2") (pintype "passive"))
      (node (ref "Q1") (pin "2") (pinfunction "S_2") (pintype "passive"))
      (node (ref "R14") (pin "1") (pinfunction "1_1") (pintype "passive"))
      (node (ref "R15") (pin "1") (pinfunction "1_1") (pintype "passive"))
      (node (ref "REG1") (pin "3") (pinfunction "IN_3") (pintype "input"))
      (node (ref "REG2") (pin "3") (pinfunction "IN_3") (pintype "input"))
      (node (ref "RN4") (pin "7") (pinfunction "2_7") (pintype "passive"))
      (node (ref "RN4") (pin "8") (pinfunction "2_8") (pintype "passive"))
    )
    (net (code "55") (name "GND") (class "Default")
      (node (ref "C1") (pin "2") (pinfunction "2_2") (pintype "passive"))
      (node (ref "C10") (pin "C") (pinfunction "-_C") (pintype "passive"))
      (node (ref "C11") (pin "2") (pinfunction "2_2") (pintype "passive"))
      (node (ref "C12") (pin "2") (pinfunction "2_2") (pintype "passive"))
      (node (ref "C13") (pin "C") (pinfunction "-_C") (pintype "passive"))
      (node (ref "C14") (pin "2") (pinfunction "2_2") (pintype "passive"))
      (node (ref "C15") (pin "2") (pinfunction "2_2") (pintype "passive"))
      (node (ref "C16") (pin "2") (pinfunction "2_2") (pintype "passive"))
      (node (ref "C18") (pin "2") (pinfunction "2_2") (pintype "passive"))
      (node (ref "C2") (pin "1") (pinfunction "1_1") (pintype "passive"))
      (node (ref "C20") (pin "1") (pinfunction "1_1") (pintype "passive"))
      (node (ref "C21") (pin "1") (pinfunction "1_1") (pintype "passive"))
      (node (ref "C22") (pin "2") (pinfunction "2_2") (pintype "passive"))
      (node (ref "C23") (pin "2") (pinfunction "2_2") (pintype "passive"))
      (node (ref "C24") (pin "2") (pinfunction "2_2") (pintype "passive"))
      (node (ref "C27") (pin "2") (pinfunction "2_2") (pintype "passive"))
      (node (ref "C29") (pin "2") (pinfunction "2_2") (pintype "passive"))
      (node (ref "C3") (pin "C") (pinfunction "-_C") (pintype "passive"))
      (node (ref "C4") (pin "C") (pinfunction "-_C") (pintype "passive"))
      (node (ref "C5") (pin "-") (pinfunction "-_-") (pintype "passive"))
      (node (ref "C6") (pin "-") (pinfunction "-_-") (pintype "passive"))
      (node (ref "C7") (pin "2") (pinfunction "2_2") (pintype "passive"))
      (node (ref "C8") (pin "1") (pinfunction "1_1") (pintype "passive"))
      (node (ref "C9") (pin "2") (pinfunction "2_2") (pintype "passive"))
      (node (ref "H1") (pin "7") (pinfunction "7_7") (pintype "passive"))
      (node (ref "H2") (pin "6") (pinfunction "6_6") (pintype "passive"))
      (node (ref "H2") (pin "7") (pinfunction "7_7") (pintype "passive"))
      (node (ref "IC1") (pin "1") (pinfunction "ADJ_1") (pintype "input"))
      (node (ref "IC2") (pin "1") (pinfunction "GND_1") (pintype "power_in"))
      (node (ref "IC3") (pin "3") (pinfunction "GND_3") (pintype "power_in"))
      (node (ref "IC3") (pin "EXP") (pinfunction "PAD_EXP") (pintype "power_in"))
      (node (ref "IC4") (pin "4") (pinfunction "V-_4") (pintype "power_in"))
      (node (ref "IC5") (pin "21") (pinfunction "AGND_21") (pintype "bidirectional"))
      (node (ref "IC5") (pin "3") (pinfunction "GND_3") (pintype "bidirectional"))
      (node (ref "IC5") (pin "5") (pinfunction "GND_5") (pintype "bidirectional"))
      (node (ref "IC7") (pin "2") (pinfunction "GND_2") (pintype "power_in"))
      (node (ref "IC7") (pin "4") (pinfunction "A1_4") (pintype "input"))
      (node (ref "IC7") (pin "5") (pinfunction "A0_5") (pintype "input"))
      (node (ref "J1") (pin "GND") (pinfunction "GND_GND") (pintype "bidirectional"))
      (node (ref "J1") (pin "GNDBREAK") (pinfunction "GNDBREAK_GNDBREAK") (pintype "bidirectional"))
      (node (ref "JP3") (pin "1") (pinfunction "GND[1]_1") (pintype "passive"))
      (node (ref "P2") (pin "6") (pinfunction "6_6") (pintype "passive"))
      (node (ref "P3") (pin "6") (pinfunction "6_6") (pintype "passive"))
      (node (ref "P4") (pin "6") (pinfunction "GND_6") (pintype "bidirectional"))
      (node (ref "P4") (pin "CD2") (pinfunction "CD2_CD2") (pintype "bidirectional"))
      (node (ref "P4") (pin "GND1") (pinfunction "SHIELD1_GND1") (pintype "bidirectional"))
      (node (ref "P4") (pin "GND2") (pinfunction "SHIELD2_GND2") (pintype "bidirectional"))
      (node (ref "Q2") (pin "2") (pinfunction "S_2") (pintype "passive"))
      (node (ref "Q3") (pin "2") (pinfunction "S_2") (pintype "passive"))
      (node (ref "REG1") (pin "1") (pinfunction "ADJ_1") (pintype "input"))
      (node (ref "REG2") (pin "1") (pinfunction "ADJ_1") (pintype "input"))
      (node (ref "RN4") (pin "4") (pinfunction "1_4") (pintype "passive"))
      (node (ref "RN6") (pin "1") (pinfunction "1_1") (pintype "passive"))
      (node (ref "RN8") (pin "1") (pinfunction "1_1") (pintype "passive"))
      (node (ref "RN8") (pin "2") (pinfunction "1_2") (pintype "passive"))
      (node (ref "RN8") (pin "3") (pinfunction "1_3") (pintype "passive"))
      (node (ref "S1") (pin "1") (pinfunction "1_1") (pintype "passive"))
      (node (ref "S1") (pin "2") (pinfunction "2_2") (pintype "passive"))
      (node (ref "SJ1") (pin "2") (pinfunction "2_2") (pintype "passive"))
      (node (ref "SJ2") (pin "1") (pinfunction "1_1") (pintype "passive"))
      (node (ref "U1") (pin "GND1") (pinfunction "GND1_GND1") (pintype "bidirectional"))
      (node (ref "U1") (pin "GND2") (pinfunction "GND2_GND2") (pintype "bidirectional"))
    )
    (net (code "56") (name "Net-(C8-Pad2)") (class "Default")
      (node (ref "C8") (pin "2") (pinfunction "2_2") (pintype "passive"))
      (node (ref "R1") (pin "1") (pinfunction "1_1") (pintype "passive"))
      (node (ref "R2") (pin "2") (pinfunction "2_2") (pintype "passive"))
      (node (ref "X1") (pin "1") (pinfunction "1_1") (pintype "passive"))
    )
    (net (code "57") (name "Net-(C15-Pad1)") (class "Default")
      (node (ref "C15") (pin "1") (pinfunction "1_1") (pintype "passive"))
      (node (ref "R3") (pin "1") (pinfunction "1_1") (pintype "passive"))
      (node (ref "X2") (pin "1") (pinfunction "1_1") (pintype "passive"))
    )
    (net (code "58") (name "Net-(C16-Pad1)") (class "Default")
      (node (ref "C16") (pin "1") (pinfunction "1_1") (pintype "passive"))
      (node (ref "R3") (pin "2") (pinfunction "2_2") (pintype "passive"))
      (node (ref "X2") (pin "2") (pinfunction "2_2") (pintype "passive"))
    )
    (net (code "59") (name "Net-(C19-Pad1)") (class "Default")
      (node (ref "C19") (pin "1") (pinfunction "1_1") (pintype "passive"))
      (node (ref "SJ3") (pin "2") (pinfunction "2_2") (pintype "passive"))
    )
    (net (code "60") (name "Net-(CD-Pad1)") (class "Default")
      (node (ref "CD") (pin "1") (pinfunction "1_1") (pintype "passive"))
      (node (ref "P4") (pin "CD1") (pinfunction "CD1_CD1") (pintype "bidirectional"))
    )
    (net (code "61") (name "Net-(D1-PadA)") (class "Default")
      (node (ref "D1") (pin "A") (pinfunction "A_A") (pintype "passive"))
      (node (ref "J1") (pin "PWR") (pinfunction "PWR_PWR") (pintype "bidirectional"))
    )
    (net (code "62") (name "Net-(F1-Pad1)") (class "Default")
      (node (ref "F1") (pin "1") (pinfunction "1_1") (pintype "passive"))
      (node (ref "P1") (pin "VBUS") (pinfunction "VBUS_VBUS") (pintype "bidirectional"))
    )
    (net (code "63") (name "Net-(IC3-UCAP)") (class "Default")
      (node (ref "C11") (pin "1") (pinfunction "1_1") (pintype "passive"))
      (node (ref "IC3") (pin "27") (pinfunction "UCAP_27") (pintype "passive"))
    )
    (net (code "64") (name "Net-(IC3-XTAL1)") (class "Default")
      (node (ref "IC3") (pin "1") (pinfunction "XTAL1_1") (pintype "bidirectional"))
      (node (ref "R2") (pin "1") (pinfunction "1_1") (pintype "passive"))
    )
    (net (code "65") (name "Net-(IC3-XTAL2)") (class "Default")
      (node (ref "C2") (pin "2") (pinfunction "2_2") (pintype "passive"))
      (node (ref "IC3") (pin "2") (pinfunction "XTAL2_2") (pintype "bidirectional"))
      (node (ref "R1") (pin "2") (pinfunction "2_2") (pintype "passive"))
      (node (ref "X1") (pin "2") (pinfunction "2_2") (pintype "passive"))
    )
    (net (code "66") (name "Net-(IC4A-+IN)") (class "Default")
      (node (ref "IC4") (pin "3") (pinfunction "+IN_3") (pintype "input"))
      (node (ref "RN4") (pin "5") (pinfunction "2_5") (pintype "passive"))
      (node (ref "RN4") (pin "6") (pinfunction "2_6") (pintype "passive"))
    )
    (net (code "67") (name "Net-(IC4A-OUT)") (class "Default")
      (node (ref "IC4") (pin "1") (pinfunction "OUT_1") (pintype "output"))
      (node (ref "IC4") (pin "5") (pinfunction "+IN_5") (pintype "input"))
    )
    (net (code "68") (name "Net-(IC4B--IN)") (class "Default")
      (node (ref "IC4") (pin "6") (pinfunction "-IN_6") (pintype "input"))
      (node (ref "IC4") (pin "7") (pinfunction "OUT_7") (pintype "output"))
      (node (ref "Q1") (pin "1") (pinfunction "G_1") (pintype "passive"))
    )
    (net (code "69") (name "Net-(IC5-ADC6)") (class "Default")
      (node (ref "A6") (pin "1") (pinfunction "1_1") (pintype "passive"))
      (node (ref "IC5") (pin "19") (pinfunction "ADC6_19") (pintype "bidirectional"))
    )
    (net (code "70") (name "Net-(IC5-ADC7)") (class "Default")
      (node (ref "A7") (pin "1") (pinfunction "1_1") (pintype "passive"))
      (node (ref "IC5") (pin "22") (pinfunction "ADC7_22") (pintype "bidirectional"))
    )
    (net (code "71") (name "Net-(IC5-PB6(XTAL1{slash}TOSC1))") (class "Default")
      (node (ref "C20") (pin "2") (pinfunction "2_2") (pintype "passive"))
      (node (ref "IC5") (pin "7") (pinfunction "PB6(XTAL1/TOSC1)_7") (pintype "bidirectional"))
      (node (ref "R7") (pin "2") (pinfunction "2_2") (pintype "passive"))
      (node (ref "X3") (pin "2") (pinfunction "2_2") (pintype "passive"))
    )
    (net (code "72") (name "Net-(IC5-PB7(XTAL2{slash}TOSC2))") (class "Default")
      (node (ref "C21") (pin "2") (pinfunction "2_2") (pintype "passive"))
      (node (ref "IC5") (pin "8") (pinfunction "PB7(XTAL2/TOSC2)_8") (pintype "bidirectional"))
      (node (ref "R7") (pin "1") (pinfunction "1_1") (pintype "passive"))
      (node (ref "X3") (pin "1") (pinfunction "1_1") (pintype "passive"))
    )
    (net (code "73") (name "Net-(IC7-SCL)") (class "Default")
      (node (ref "IC7") (pin "1") (pinfunction "SCL_1") (pintype "bidirectional"))
      (node (ref "R15") (pin "2") (pinfunction "2_2") (pintype "passive"))
      (node (ref "SJ6") (pin "2") (pinfunction "2_2") (pintype "passive"))
    )
    (net (code "74") (name "Net-(IC7-SDA)") (class "Default")
      (node (ref "IC7") (pin "3") (pinfunction "SDA_3") (pintype "bidirectional"))
      (node (ref "R14") (pin "2") (pinfunction "2_2") (pintype "passive"))
      (node (ref "SJ5") (pin "2") (pinfunction "2_2") (pintype "passive"))
    )
    (net (code "75") (name "Net-(JP3-V+[3])") (class "Default")
      (node (ref "JP3") (pin "3") (pinfunction "V+[3]_3") (pintype "passive"))
      (node (ref "U1") (pin "P$9") (pinfunction "V+_P$9") (pintype "bidirectional"))
    )
    (net (code "76") (name "Net-(JP3-V-[2])") (class "Default")
      (node (ref "JP3") (pin "2") (pinfunction "V-[2]_2") (pintype "passive"))
      (node (ref "U1") (pin "P$10") (pinfunction "V-_P$10") (pintype "bidirectional"))
    )
    (net (code "77") (name "Net-(L3-Pad1)") (class "Default")
      (node (ref "L3") (pin "1") (pinfunction "1_1") (pintype "passive"))
      (node (ref "P1") (pin "FIX1") (pinfunction "FIX1_FIX1") (pintype "bidirectional"))
      (node (ref "P1") (pin "FIX2") (pinfunction "FIX2_FIX2") (pintype "bidirectional"))
      (node (ref "P1") (pin "PIN1") (pinfunction "PIN1_PIN1") (pintype "bidirectional"))
      (node (ref "P1") (pin "PIN2") (pinfunction "PIN2_PIN2") (pintype "bidirectional"))
      (node (ref "P1") (pin "TAB1") (pinfunction "TAB1_TAB1") (pintype "bidirectional"))
      (node (ref "P1") (pin "TAB2") (pinfunction "TAB2_TAB2") (pintype "bidirectional"))
      (node (ref "Z1") (pin "2") (pinfunction "2_2") (pintype "passive"))
      (node (ref "Z2") (pin "2") (pinfunction "2_2") (pintype "passive"))
    )
    (net (code "78") (name "Net-(LED5-PadC)") (class "Default")
      (node (ref "LED5") (pin "C") (pinfunction "C_C") (pintype "passive"))
      (node (ref "RN3") (pin "1") (pinfunction "1_1") (pintype "passive"))
    )
    (net (code "79") (name "Net-(LED10-PadC)") (class "Default")
      (node (ref "LED10") (pin "C") (pinfunction "C_C") (pintype "passive"))
      (node (ref "R8") (pin "2") (pinfunction "2_2") (pintype "passive"))
    )
    (net (code "80") (name "Net-(P1-PadD+)") (class "Default")
      (node (ref "P1") (pin "D+") (pinfunction "D+_D+") (pintype "bidirectional"))
      (node (ref "R5") (pin "2") (pinfunction "2_2") (pintype "passive"))
      (node (ref "Z1") (pin "1") (pinfunction "1_1") (pintype "passive"))
    )
    (net (code "81") (name "Net-(P1-PadD-)") (class "Default")
      (node (ref "P1") (pin "D-") (pinfunction "D-_D-") (pintype "bidirectional"))
      (node (ref "R4") (pin "2") (pinfunction "2_2") (pintype "passive"))
      (node (ref "Z2") (pin "1") (pinfunction "1_1") (pintype "passive"))
    )
    (net (code "82") (name "Net-(P4-CS)") (class "Default")
      (node (ref "P4") (pin "2") (pinfunction "CS_2") (pintype "bidirectional"))
      (node (ref "RN6") (pin "4") (pinfunction "1_4") (pintype "passive"))
      (node (ref "RN8") (pin "8") (pinfunction "2_8") (pintype "passive"))
    )
    (net (code "83") (name "Net-(P4-DI)") (class "Default")
      (node (ref "P4") (pin "3") (pinfunction "DI_3") (pintype "bidirectional"))
      (node (ref "RN6") (pin "3") (pinfunction "1_3") (pintype "passive"))
      (node (ref "RN8") (pin "6") (pinfunction "2_6") (pintype "passive"))
    )
    (net (code "84") (name "Net-(P4-SCK)") (class "Default")
      (node (ref "P4") (pin "5") (pinfunction "SCK_5") (pintype "bidirectional"))
      (node (ref "RN6") (pin "2") (pinfunction "1_2") (pintype "passive"))
      (node (ref "RN8") (pin "7") (pinfunction "2_7") (pintype "passive"))
    )
    (net (code "85") (name "Net-(Q2-D)") (class "Default")
      (node (ref "Q2") (pin "3") (pinfunction "D_3") (pintype "passive"))
      (node (ref "R8") (pin "1") (pinfunction "1_1") (pintype "passive"))
    )
    (net (code "86") (name "Net-(RN1A-2)") (class "Default")
      (node (ref "LED1") (pin "C") (pinfunction "C_C") (pintype "passive"))
      (node (ref "RN1") (pin "8") (pinfunction "2_8") (pintype "passive"))
    )
    (net (code "87") (name "Net-(RN1B-2)") (class "Default")
      (node (ref "LED3") (pin "C") (pinfunction "C_C") (pintype "passive"))
      (node (ref "RN1") (pin "7") (pinfunction "2_7") (pintype "passive"))
    )
    (net (code "88") (name "Net-(RN1C-2)") (class "Default")
      (node (ref "LED4") (pin "C") (pinfunction "C_C") (pintype "passive"))
      (node (ref "RN1") (pin "6") (pinfunction "2_6") (pintype "passive"))
    )
    (net (code "89") (name "Net-(RN1D-2)") (class "Default")
      (node (ref "LED7") (pin "C") (pinfunction "C_C") (pintype "passive"))
      (node (ref "RN1") (pin "5") (pinfunction "2_5") (pintype "passive"))
    )
    (net (code "90") (name "Net-(RN2B-1)") (class "Default")
      (node (ref "RN2") (pin "2") (pinfunction "1_2") (pintype "passive"))
      (node (ref "U1") (pin "P$12") (pinfunction "Y-_P$12") (pintype "bidirectional"))
    )
    (net (code "91") (name "Net-(RN2C-2)") (class "Default")
      (node (ref "LED8") (pin "C") (pinfunction "C_C") (pintype "passive"))
      (node (ref "RN2") (pin "6") (pinfunction "2_6") (pintype "passive"))
    )
    (net (code "92") (name "Net-(RN2D-2)") (class "Default")
      (node (ref "LED9") (pin "C") (pinfunction "C_C") (pintype "passive"))
      (node (ref "RN2") (pin "5") (pinfunction "2_5") (pintype "passive"))
    )
    (net (code "93") (name "Net-(RN3B-1)") (class "Default")
      (node (ref "LED6") (pin "C") (pinfunction "C_C") (pintype "passive"))
      (node (ref "RN3") (pin "2") (pinfunction "1_2") (pintype "passive"))
    )
    (net (code "94") (name "Net-(RN5A-2)") (class "Default")
      (node (ref "C23") (pin "1") (pinfunction "1_1") (pintype "passive"))
      (node (ref "RN5") (pin "7") (pinfunction "2_7") (pintype "passive"))
      (node (ref "RN5") (pin "8") (pinfunction "2_8") (pintype "passive"))
    )
    (net (code "95") (name "Net-(RN5C-2)") (class "Default")
      (node (ref "C24") (pin "1") (pinfunction "1_1") (pintype "passive"))
      (node (ref "RN5") (pin "5") (pinfunction "2_5") (pintype "passive"))
      (node (ref "RN5") (pin "6") (pinfunction "2_6") (pintype "passive"))
    )
    (net (code "96") (name "Net-(RN6A-2)") (class "Default")
      (node (ref "LED2") (pin "C") (pinfunction "C_C") (pintype "passive"))
      (node (ref "RN6") (pin "8") (pinfunction "2_8") (pintype "passive"))
    )
    (net (code "97") (name "Net-(U1-G-)") (class "Default")
      (node (ref "RN2") (pin "1") (pinfunction "1_1") (pintype "passive"))
      (node (ref "U1") (pin "P$14") (pinfunction "G-_P$14") (pintype "bidirectional"))
    )
    (net (code "98") (name "unconnected-(H2-Pad1)") (class "Default")
      (node (ref "H2") (pin "1") (pinfunction "1_1") (pintype "passive"))
    )
    (net (code "99") (name "unconnected-(H2-Pad2)") (class "Default")
      (node (ref "H2") (pin "2") (pinfunction "2_2") (pintype "passive"))
    )
    (net (code "100") (name "unconnected-(IC3-(RTS)PD6-Pad12)") (class "Default")
      (node (ref "IC3") (pin "12") (pinfunction "(RTS)PD6_12") (pintype "bidirectional"))
    )
    (net (code "101") (name "unconnected-(IC3-(SS)PB0-Pad14)") (class "Default")
      (node (ref "IC3") (pin "14") (pinfunction "(SS)PB0_14") (pintype "bidirectional"))
    )
    (net (code "102") (name "unconnected-(IC3-PB4-Pad18)") (class "Default")
      (node (ref "IC3") (pin "18") (pinfunction "PB4_18") (pintype "bidirectional"))
    )
    (net (code "103") (name "unconnected-(IC3-PB5-Pad19)") (class "Default")
      (node (ref "IC3") (pin "19") (pinfunction "PB5_19") (pintype "bidirectional"))
    )
    (net (code "104") (name "unconnected-(IC3-PB6-Pad20)") (class "Default")
      (node (ref "IC3") (pin "20") (pinfunction "PB6_20") (pintype "bidirectional"))
    )
    (net (code "105") (name "unconnected-(IC3-PB7-Pad21)") (class "Default")
      (node (ref "IC3") (pin "21") (pinfunction "PB7_21") (pintype "bidirectional"))
    )
    (net (code "106") (name "unconnected-(IC3-PC2-Pad5)") (class "Default")
      (node (ref "IC3") (pin "5") (pinfunction "PC2_5") (pintype "bidirectional"))
    )
    (net (code "107") (name "unconnected-(IC3-PC4-Pad26)") (class "Default")
      (node (ref "IC3") (pin "26") (pinfunction "PC4_26") (pintype "bidirectional"))
    )
    (net (code "108") (name "unconnected-(IC3-PC5-Pad25)") (class "Default")
      (node (ref "IC3") (pin "25") (pinfunction "PC5_25") (pintype "bidirectional"))
    )
    (net (code "109") (name "unconnected-(IC3-PC6-Pad23)") (class "Default")
      (node (ref "IC3") (pin "23") (pinfunction "PC6_23") (pintype "bidirectional"))
    )
    (net (code "110") (name "unconnected-(IC3-PC7-Pad22)") (class "Default")
      (node (ref "IC3") (pin "22") (pinfunction "PC7_22") (pintype "bidirectional"))
    )
    (net (code "111") (name "unconnected-(IC3-PD0-Pad6)") (class "Default")
      (node (ref "IC3") (pin "6") (pinfunction "PD0_6") (pintype "bidirectional"))
    )
    (net (code "112") (name "unconnected-(IC3-PD1-Pad7)") (class "Default")
      (node (ref "IC3") (pin "7") (pinfunction "PD1_7") (pintype "bidirectional"))
    )
    (net (code "113") (name "unconnected-(IC8-1V2O-Pad22)") (class "Default")
      (node (ref "IC8") (pin "22") (pinfunction "1V2O_22") (pintype "passive"))
    )
    (net (code "114") (name "unconnected-(IC8-ACTLED-Pad27)") (class "Default")
      (node (ref "IC8") (pin "27") (pinfunction "ACTLED_27") (pintype "passive"))
    )
    (net (code "115") (name "unconnected-(IC8-AGND-Pad3)") (class "Default")
      (node (ref "IC8") (pin "3") (pinfunction "AGND_3") (pintype "passive"))
    )
    (net (code "116") (name "unconnected-(IC8-AGND-Pad9)") (class "Default")
      (node (ref "IC8") (pin "9") (pinfunction "AGND_9") (pintype "passive"))
    )
    (net (code "117") (name "unconnected-(IC8-AGND-Pad14)") (class "Default")
      (node (ref "IC8") (pin "14") (pinfunction "AGND_14") (pintype "passive"))
    )
    (net (code "118") (name "unconnected-(IC8-AGND-Pad16)") (class "Default")
      (node (ref "IC8") (pin "16") (pinfunction "AGND_16") (pintype "passive"))
    )
    (net (code "119") (name "unconnected-(IC8-AGND-Pad19)") (class "Default")
      (node (ref "IC8") (pin "19") (pinfunction "AGND_19") (pintype "passive"))
    )
    (net (code "120") (name "unconnected-(IC8-AGND-Pad48)") (class "Default")
      (node (ref "IC8") (pin "48") (pinfunction "AGND_48") (pintype "passive"))
    )
    (net (code "121") (name "unconnected-(IC8-AVDD-Pad4)") (class "Default")
      (node (ref "IC8") (pin "4") (pinfunction "AVDD_4") (pintype "passive"))
    )
    (net (code "122") (name "unconnected-(IC8-AVDD-Pad8)") (class "Default")
      (node (ref "IC8") (pin "8") (pinfunction "AVDD_8") (pintype "passive"))
    )
    (net (code "123") (name "unconnected-(IC8-AVDD-Pad11)") (class "Default")
      (node (ref "IC8") (pin "11") (pinfunction "AVDD_11") (pintype "passive"))
    )
    (net (code "124") (name "unconnected-(IC8-AVDD-Pad15)") (class "Default")
      (node (ref "IC8") (pin "15") (pinfunction "AVDD_15") (pintype "passive"))
    )
    (net (code "125") (name "unconnected-(IC8-AVDD-Pad17)") (class "Default")
      (node (ref "IC8") (pin "17") (pinfunction "AVDD_17") (pintype "passive"))
    )
    (net (code "126") (name "unconnected-(IC8-AVDD-Pad21)") (class "Default")
      (node (ref "IC8") (pin "21") (pinfunction "AVDD_21") (pintype "passive"))
    )
    (net (code "127") (name "unconnected-(IC8-DNC-Pad7)") (class "Default")
      (node (ref "IC8") (pin "7") (pinfunction "DNC_7") (pintype "passive"))
    )
    (net (code "128") (name "unconnected-(IC8-DUPLED-Pad26)") (class "Default")
      (node (ref "IC8") (pin "26") (pinfunction "DUPLED_26") (pintype "passive"))
    )
    (net (code "129") (name "unconnected-(IC8-EXRES1-Pad10)") (class "Default")
      (node (ref "IC8") (pin "10") (pinfunction "EXRES1_10") (pintype "passive"))
    )
    (net (code "130") (name "unconnected-(IC8-GND-Pad29)") (class "Default")
      (node (ref "IC8") (pin "29") (pinfunction "GND_29") (pintype "passive"))
    )
    (net (code "131") (name "unconnected-(IC8-INT_N-Pad36)") (class "Default")
      (node (ref "IC8") (pin "36") (pinfunction "INT_N_36") (pintype "passive"))
    )
    (net (code "132") (name "unconnected-(IC8-LINKLED-Pad25)") (class "Default")
      (node (ref "IC8") (pin "25") (pinfunction "LINKLED_25") (pintype "passive"))
    )
    (net (code "133") (name "unconnected-(IC8-MISO-Pad34)") (class "Default")
      (node (ref "IC8") (pin "34") (pinfunction "MISO_34") (pintype "passive"))
    )
    (net (code "134") (name "unconnected-(IC8-MOSI-Pad35)") (class "Default")
      (node (ref "IC8") (pin "35") (pinfunction "MOSI_35") (pintype "passive"))
    )
    (net (code "135") (name "unconnected-(IC8-NC-Pad12)") (class "Default")
      (node (ref "IC8") (pin "12") (pinfunction "NC_12") (pintype "passive"))
    )
    (net (code "136") (name "unconnected-(IC8-NC-Pad13)") (class "Default")
      (node (ref "IC8") (pin "13") (pinfunction "NC_13") (pintype "passive"))
    )
    (net (code "137") (name "unconnected-(IC8-NC-Pad46)") (class "Default")
      (node (ref "IC8") (pin "46") (pinfunction "NC_46") (pintype "passive"))
    )
    (net (code "138") (name "unconnected-(IC8-NC-Pad47)") (class "Default")
      (node (ref "IC8") (pin "47") (pinfunction "NC_47") (pintype "passive"))
    )
    (net (code "139") (name "unconnected-(IC8-PMODE0-Pad45)") (class "Default")
      (node (ref "IC8") (pin "45") (pinfunction "PMODE0_45") (pintype "passive"))
    )
    (net (code "140") (name "unconnected-(IC8-PMODE1-Pad44)") (class "Default")
      (node (ref "IC8") (pin "44") (pinfunction "PMODE1_44") (pintype "passive"))
    )
    (net (code "141") (name "unconnected-(IC8-PMODE2-Pad43)") (class "Default")
      (node (ref "IC8") (pin "43") (pinfunction "PMODE2_43") (pintype "passive"))
    )
    (net (code "142") (name "unconnected-(IC8-RST_N-Pad37)") (class "Default")
      (node (ref "IC8") (pin "37") (pinfunction "RST_N_37") (pintype "passive"))
    )
    (net (code "143") (name "unconnected-(IC8-RSVD-Pad23)") (class "Default")
      (node (ref "IC8") (pin "23") (pinfunction "RSVD_23") (pintype "passive"))
    )
    (net (code "144") (name "unconnected-(IC8-RSVD-Pad38)") (class "Default")
      (node (ref "IC8") (pin "38") (pinfunction "RSVD_38") (pintype "passive"))
    )
    (net (code "145") (name "unconnected-(IC8-RSVD-Pad39)") (class "Default")
      (node (ref "IC8") (pin "39") (pinfunction "RSVD_39") (pintype "passive"))
    )
    (net (code "146") (name "unconnected-(IC8-RSVD-Pad40)") (class "Default")
      (node (ref "IC8") (pin "40") (pinfunction "RSVD_40") (pintype "passive"))
    )
    (net (code "147") (name "unconnected-(IC8-RSVD-Pad41)") (class "Default")
      (node (ref "IC8") (pin "41") (pinfunction "RSVD_41") (pintype "passive"))
    )
    (net (code "148") (name "unconnected-(IC8-RSVD-Pad42)") (class "Default")
      (node (ref "IC8") (pin "42") (pinfunction "RSVD_42") (pintype "passive"))
    )
    (net (code "149") (name "unconnected-(IC8-RXN-Pad5)") (class "Default")
      (node (ref "IC8") (pin "5") (pinfunction "RXN_5") (pintype "passive"))
    )
    (net (code "150") (name "unconnected-(IC8-RXP-Pad6)") (class "Default")
      (node (ref "IC8") (pin "6") (pinfunction "RXP_6") (pintype "passive"))
    )
    (net (code "151") (name "unconnected-(IC8-SCLK-Pad33)") (class "Default")
      (node (ref "IC8") (pin "33") (pinfunction "SCLK_33") (pintype "passive"))
    )
    (net (code "152") (name "unconnected-(IC8-SCS_N-Pad32)") (class "Default")
      (node (ref "IC8") (pin "32") (pinfunction "SCS_N_32") (pintype "passive"))
    )
    (net (code "153") (name "unconnected-(IC8-SPDLED-Pad24)") (class "Default")
      (node (ref "IC8") (pin "24") (pinfunction "SPDLED_24") (pintype "passive"))
    )
    (net (code "154") (name "unconnected-(IC8-TOCAP-Pad20)") (class "Default")
      (node (ref "IC8") (pin "20") (pinfunction "TOCAP_20") (pintype "passive"))
    )
    (net (code "155") (name "unconnected-(IC8-TXN-Pad1)") (class "Default")
      (node (ref "IC8") (pin "1") (pinfunction "TXN_1") (pintype "passive"))
    )
    (net (code "156") (name "unconnected-(IC8-TXP-Pad2)") (class "Default")
      (node (ref "IC8") (pin "2") (pinfunction "TXP_2") (pintype "passive"))
    )
    (net (code "157") (name "unconnected-(IC8-VBG-Pad18)") (class "Default")
      (node (ref "IC8") (pin "18") (pinfunction "VBG_18") (pintype "passive"))
    )
    (net (code "158") (name "unconnected-(IC8-VDD-Pad28)") (class "Default")
      (node (ref "IC8") (pin "28") (pinfunction "VDD_28") (pintype "passive"))
    )
    (net (code "159") (name "unconnected-(IC8-XI{slash}CLKIN-Pad30)") (class "Default")
      (node (ref "IC8") (pin "30") (pinfunction "XI/CLKIN_30") (pintype "passive"))
    )
    (net (code "160") (name "unconnected-(IC8-XO-Pad31)") (class "Default")
      (node (ref "IC8") (pin "31") (pinfunction "XO_31") (pintype "passive"))
    )
    (net (code "161") (name "unconnected-(JP3-PadMNT1)") (class "Default")
      (node (ref "JP3") (pin "MNT1") (pinfunction "MNT1_MNT1") (pintype "passive"))
    )
    (net (code "162") (name "unconnected-(JP3-PadMNT2)") (class "Default")
      (node (ref "JP3") (pin "MNT2") (pinfunction "MNT2_MNT2") (pintype "passive"))
    )
    (net (code "163") (name "unconnected-(P1-PadID)") (class "Default")
      (node (ref "P1") (pin "ID") (pinfunction "ID_ID") (pintype "bidirectional"))
    )
    (net (code "164") (name "unconnected-(P4-NC-Pad1)") (class "Default")
      (node (ref "P4") (pin "1") (pinfunction "NC_1") (pintype "bidirectional"))
    )
    (net (code "165") (name "unconnected-(P4-RSV-Pad8)") (class "Default")
      (node (ref "P4") (pin "8") (pinfunction "RSV_8") (pintype "bidirectional"))
    )
    (net (code "166") (name "unconnected-(RN7-Pad1)") (class "Default")
      (node (ref "RN7") (pin "1") (pinfunction "1_1") (pintype "passive"))
    )
    (net (code "167") (name "unconnected-(RN7A-2-Pad8)") (class "Default")
      (node (ref "RN7") (pin "8") (pinfunction "2_8") (pintype "passive"))
    )
    (net (code "168") (name "unconnected-(RN7C-1-Pad3)") (class "Default")
      (node (ref "RN7") (pin "3") (pinfunction "1_3") (pintype "passive"))
    )
    (net (code "169") (name "unconnected-(RN7C-2-Pad6)") (class "Default")
      (node (ref "RN7") (pin "6") (pinfunction "2_6") (pintype "passive"))
    )
    (net (code "170") (name "unconnected-(RN8D-1-Pad4)") (class "Default")
      (node (ref "RN8") (pin "4") (pinfunction "1_4") (pintype "passive"))
    )
    (net (code "171") (name "unconnected-(RN8D-2-Pad5)") (class "Default")
      (node (ref "RN8") (pin "5") (pinfunction "2_5") (pintype "passive"))
    )
  )
)
